# monopoly.net
KiCad netlist of a schematic drawn in EAGLE
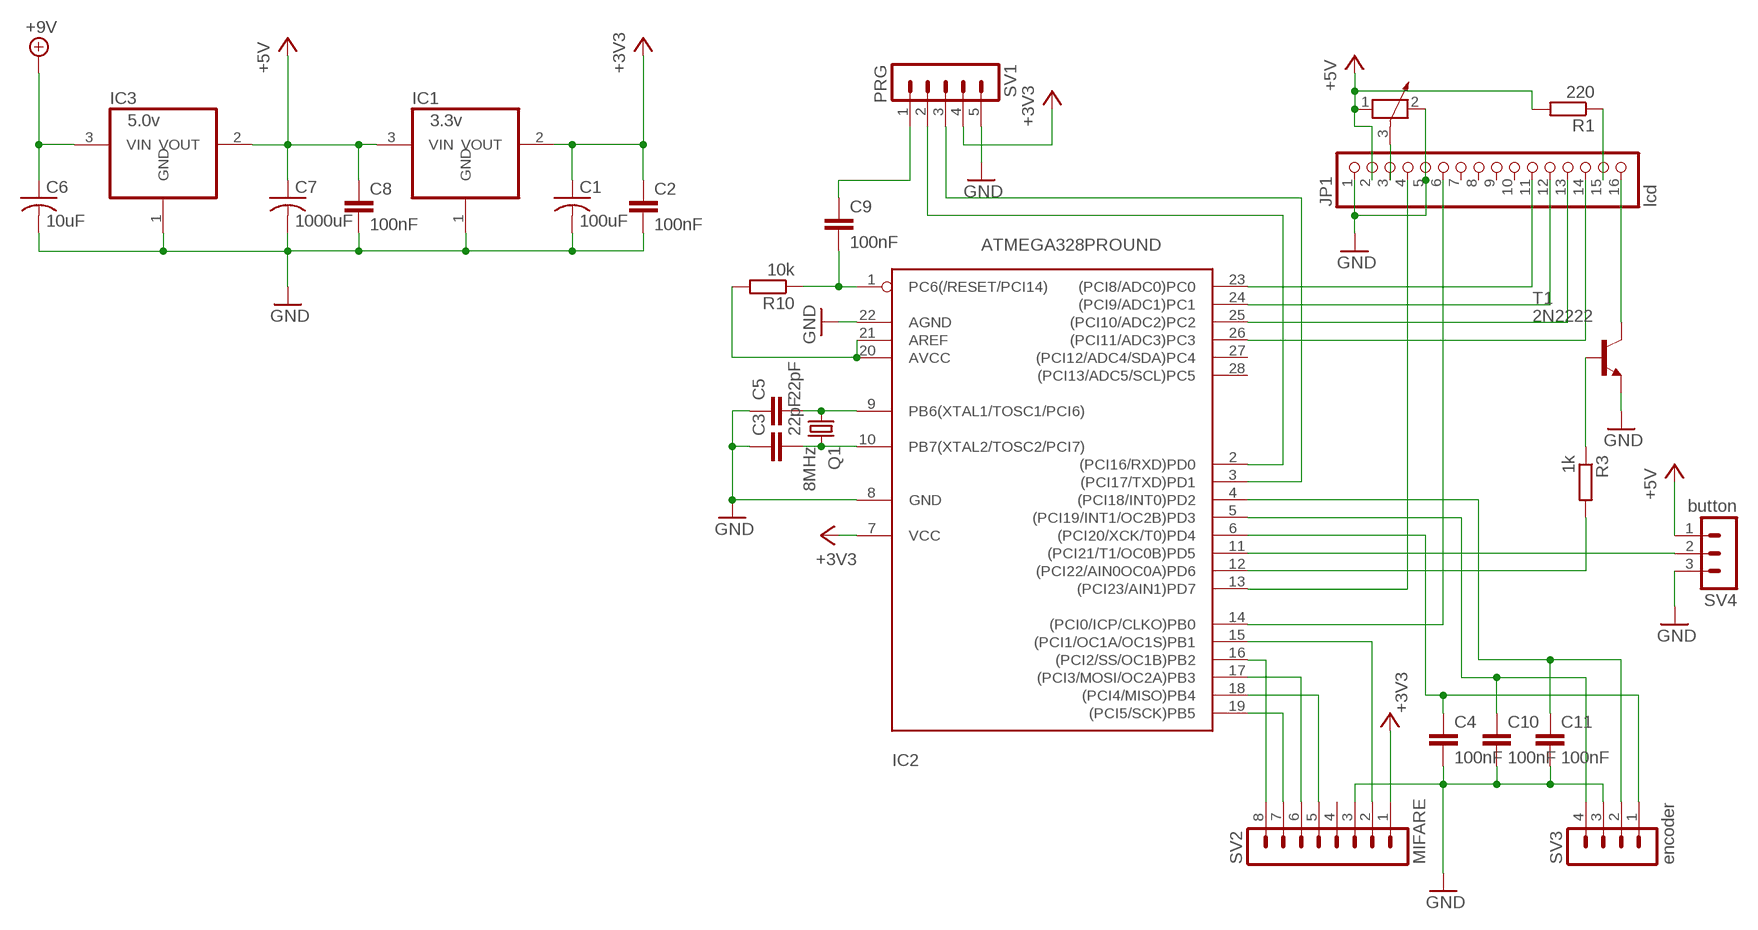
[diagram p0: schematic, sheet 1]

(export (version "E")
  (design (tool "Eeschema 10.0.6"))
  (components
    (comp (ref "C1")
      (value "100uF")
      (footprint "eagle-import:C025-024X044")
      (libsource (lib "eagle-import") (part "C-US025-024X044"))
    )
    (comp (ref "C2")
      (value "100nF")
      (footprint "eagle-import:C2.5-3")
      (libsource (lib "eagle-import") (part "C2,5-3"))
    )
    (comp (ref "C3")
      (value "22pF")
      (footprint "eagle-import:C2.5-3")
      (libsource (lib "eagle-import") (part "C2,5-3"))
    )
    (comp (ref "C4")
      (value "100nF")
      (footprint "eagle-import:C2.5-3")
      (libsource (lib "eagle-import") (part "C2,5-3"))
    )
    (comp (ref "C5")
      (value "22pF")
      (footprint "eagle-import:C2.5-3")
      (libsource (lib "eagle-import") (part "C2,5-3"))
    )
    (comp (ref "C6")
      (value "10uF")
      (footprint "eagle-import:C025-024X044")
      (libsource (lib "eagle-import") (part "C-US025-024X044"))
    )
    (comp (ref "C7")
      (value "1000uF")
      (footprint "eagle-import:C025-024X044")
      (libsource (lib "eagle-import") (part "C-US025-024X044"))
    )
    (comp (ref "C8")
      (value "100nF")
      (footprint "eagle-import:C2.5-3")
      (libsource (lib "eagle-import") (part "C2,5-3"))
    )
    (comp (ref "C9")
      (value "100nF")
      (footprint "eagle-import:C2.5-3")
      (libsource (lib "eagle-import") (part "C2,5-3"))
    )
    (comp (ref "C10")
      (value "100nF")
      (footprint "eagle-import:C2.5-3")
      (libsource (lib "eagle-import") (part "C2,5-3"))
    )
    (comp (ref "C11")
      (value "100nF")
      (footprint "eagle-import:C2.5-3")
      (libsource (lib "eagle-import") (part "C2,5-3"))
    )
    (comp (ref "IC1")
      (value "3.3v")
      (footprint "eagle-import:SOT223")
      (fields (field (name "MPN") "REG1117"))
      (libsource (lib "eagle-import") (part "REG1117"))
    )
    (comp (ref "IC2")
      (value "ATMEGA328PROUND")
      (footprint "eagle-import:DIL28-3-ROUND")
      (libsource (lib "eagle-import") (part "ATMEGA328PROUND"))
    )
    (comp (ref "IC3")
      (value "5.0v")
      (footprint "eagle-import:SOT223")
      (fields (field (name "MPN") "REG1117"))
      (libsource (lib "eagle-import") (part "REG1117"))
    )
    (comp (ref "JP1")
      (value "lcd")
      (footprint "eagle-import:1X16")
      (libsource (lib "eagle-import") (part "PINHD-1X16"))
    )
    (comp (ref "Q1")
      (value "8MHz")
      (footprint "eagle-import:HC18U-V")
      (libsource (lib "eagle-import") (part "CRYSTALHC18U-V"))
    )
    (comp (ref "R1")
      (value "220")
      (footprint "eagle-import:0204_7")
      (libsource (lib "eagle-import") (part "R0204/7"))
    )
    (comp (ref "R2")
      (value "POTENTIOMETER_PT_SPIN")
      (footprint "eagle-import:PT-SPIN")
      (libsource (lib "eagle-import") (part "POTENTIOMETER_PT_SPIN"))
    )
    (comp (ref "R3")
      (value "1k")
      (footprint "eagle-import:0204_7")
      (libsource (lib "eagle-import") (part "R0204/7"))
    )
    (comp (ref "R10")
      (value "10k")
      (footprint "eagle-import:0204_7")
      (libsource (lib "eagle-import") (part "R0204/7"))
    )
    (comp (ref "SV1")
      (value "PRG")
      (footprint "eagle-import:MA05-1")
      (libsource (lib "eagle-import") (part "MA05-1"))
    )
    (comp (ref "SV2")
      (value "MIFARE")
      (footprint "eagle-import:MA08-1W")
      (libsource (lib "eagle-import") (part "MA08-1W"))
    )
    (comp (ref "SV3")
      (value "encoder")
      (footprint "eagle-import:MA04-1")
      (libsource (lib "eagle-import") (part "MA04-1"))
    )
    (comp (ref "SV4")
      (value "button")
      (footprint "eagle-import:MA03-1")
      (libsource (lib "eagle-import") (part "MA03-1"))
    )
    (comp (ref "T1")
      (value "2N2222")
      (footprint "eagle-import:TO18")
      (libsource (lib "eagle-import") (part "2N2222"))
    )
  )
  (nets
    (net (code "1") (name "+3V3") (class "Default")
      (node (ref "C1") (pin "1") (pinfunction "1_1") (pintype "passive"))
      (node (ref "C2") (pin "1") (pinfunction "1_1") (pintype "passive"))
      (node (ref "IC1") (pin "2") (pinfunction "VOUT_2") (pintype "output"))
      (node (ref "IC2") (pin "7") (pinfunction "VCC_7") (pintype "bidirectional"))
      (node (ref "SV1") (pin "4") (pinfunction "4_4") (pintype "passive"))
      (node (ref "SV2") (pin "1") (pinfunction "1_1") (pintype "passive"))
    )
    (net (code "2") (name "+5V") (class "Default")
      (node (ref "C7") (pin "1") (pinfunction "1_1") (pintype "passive"))
      (node (ref "C8") (pin "1") (pinfunction "1_1") (pintype "passive"))
      (node (ref "IC1") (pin "3") (pinfunction "VIN_3") (pintype "input"))
      (node (ref "IC3") (pin "2") (pinfunction "VOUT_2") (pintype "output"))
      (node (ref "JP1") (pin "2") (pinfunction "2_2") (pintype "passive"))
      (node (ref "R1") (pin "2") (pinfunction "2_2") (pintype "passive"))
      (node (ref "R2") (pin "1") (pinfunction "1_1") (pintype "passive"))
      (node (ref "SV4") (pin "1") (pinfunction "1_1") (pintype "passive"))
    )
    (net (code "3") (name "+9V") (class "Default")
      (node (ref "C6") (pin "1") (pinfunction "1_1") (pintype "passive"))
      (node (ref "IC3") (pin "3") (pinfunction "VIN_3") (pintype "input"))
    )
    (net (code "4") (name "GND") (class "Default")
      (node (ref "C1") (pin "2") (pinfunction "2_2") (pintype "passive"))
      (node (ref "C10") (pin "2") (pinfunction "2_2") (pintype "passive"))
      (node (ref "C11") (pin "2") (pinfunction "2_2") (pintype "passive"))
      (node (ref "C2") (pin "2") (pinfunction "2_2") (pintype "passive"))
      (node (ref "C3") (pin "1") (pinfunction "1_1") (pintype "passive"))
      (node (ref "C4") (pin "2") (pinfunction "2_2") (pintype "passive"))
      (node (ref "C5") (pin "1") (pinfunction "1_1") (pintype "passive"))
      (node (ref "C6") (pin "2") (pinfunction "2_2") (pintype "passive"))
      (node (ref "C7") (pin "2") (pinfunction "2_2") (pintype "passive"))
      (node (ref "C8") (pin "2") (pinfunction "2_2") (pintype "passive"))
      (node (ref "IC1") (pin "1") (pinfunction "GND_1") (pintype "power_in"))
      (node (ref "IC2") (pin "22") (pinfunction "AGND_22") (pintype "bidirectional"))
      (node (ref "IC2") (pin "8") (pinfunction "GND_8") (pintype "bidirectional"))
      (node (ref "IC3") (pin "1") (pinfunction "GND_1") (pintype "power_in"))
      (node (ref "JP1") (pin "1") (pinfunction "1_1") (pintype "passive"))
      (node (ref "JP1") (pin "5") (pinfunction "5_5") (pintype "passive"))
      (node (ref "R2") (pin "2") (pinfunction "2_2") (pintype "passive"))
      (node (ref "SV1") (pin "5") (pinfunction "5_5") (pintype "passive"))
      (node (ref "SV2") (pin "3") (pinfunction "3_3") (pintype "passive"))
      (node (ref "SV3") (pin "3") (pinfunction "3_3") (pintype "passive"))
      (node (ref "SV4") (pin "3") (pinfunction "3_3") (pintype "passive"))
      (node (ref "T1") (pin "1") (pinfunction "E_1") (pintype "passive"))
    )
    (net (code "5") (name "Net-(C9-Pad1)") (class "Default")
      (node (ref "C9") (pin "1") (pinfunction "1_1") (pintype "passive"))
      (node (ref "SV1") (pin "1") (pinfunction "1_1") (pintype "passive"))
    )
    (net (code "6") (name "Net-(IC2-(PCI0{slash}ICP{slash}CLKO)PB0)") (class "Default")
      (node (ref "IC2") (pin "14") (pinfunction "(PCI0/ICP/CLKO)PB0_14") (pintype "bidirectional"))
      (node (ref "JP1") (pin "6") (pinfunction "6_6") (pintype "passive"))
    )
    (net (code "7") (name "Net-(IC2-(PCI1{slash}OC1A{slash}OC1S)PB1)") (class "Default")
      (node (ref "IC2") (pin "15") (pinfunction "(PCI1/OC1A/OC1S)PB1_15") (pintype "bidirectional"))
      (node (ref "SV2") (pin "2") (pinfunction "2_2") (pintype "passive"))
    )
    (net (code "8") (name "Net-(IC2-(PCI2{slash}SS{slash}OC1B)PB2)") (class "Default")
      (node (ref "IC2") (pin "16") (pinfunction "(PCI2/SS/OC1B)PB2_16") (pintype "bidirectional"))
      (node (ref "SV2") (pin "8") (pinfunction "8_8") (pintype "passive"))
    )
    (net (code "9") (name "Net-(IC2-(PCI3{slash}MOSI{slash}OC2A)PB3)") (class "Default")
      (node (ref "IC2") (pin "17") (pinfunction "(PCI3/MOSI/OC2A)PB3_17") (pintype "bidirectional"))
      (node (ref "SV2") (pin "6") (pinfunction "6_6") (pintype "passive"))
    )
    (net (code "10") (name "Net-(IC2-(PCI4{slash}MISO)PB4)") (class "Default")
      (node (ref "IC2") (pin "18") (pinfunction "(PCI4/MISO)PB4_18") (pintype "bidirectional"))
      (node (ref "SV2") (pin "5") (pinfunction "5_5") (pintype "passive"))
    )
    (net (code "11") (name "Net-(IC2-(PCI5{slash}SCK)PB5)") (class "Default")
      (node (ref "IC2") (pin "19") (pinfunction "(PCI5/SCK)PB5_19") (pintype "bidirectional"))
      (node (ref "SV2") (pin "7") (pinfunction "7_7") (pintype "passive"))
    )
    (net (code "12") (name "Net-(IC2-(PCI8{slash}ADC0)PC0)") (class "Default")
      (node (ref "IC2") (pin "23") (pinfunction "(PCI8/ADC0)PC0_23") (pintype "bidirectional"))
      (node (ref "JP1") (pin "11") (pinfunction "11_11") (pintype "passive"))
    )
    (net (code "13") (name "Net-(IC2-(PCI9{slash}ADC1)PC1)") (class "Default")
      (node (ref "IC2") (pin "24") (pinfunction "(PCI9/ADC1)PC1_24") (pintype "bidirectional"))
      (node (ref "JP1") (pin "12") (pinfunction "12_12") (pintype "passive"))
    )
    (net (code "14") (name "Net-(IC2-(PCI10{slash}ADC2)PC2)") (class "Default")
      (node (ref "IC2") (pin "25") (pinfunction "(PCI10/ADC2)PC2_25") (pintype "bidirectional"))
      (node (ref "JP1") (pin "13") (pinfunction "13_13") (pintype "passive"))
    )
    (net (code "15") (name "Net-(IC2-(PCI11{slash}ADC3)PC3)") (class "Default")
      (node (ref "IC2") (pin "26") (pinfunction "(PCI11/ADC3)PC3_26") (pintype "bidirectional"))
      (node (ref "JP1") (pin "14") (pinfunction "14_14") (pintype "passive"))
    )
    (net (code "16") (name "Net-(IC2-(PCI16{slash}RXD)PD0)") (class "Default")
      (node (ref "IC2") (pin "2") (pinfunction "(PCI16/RXD)PD0_2") (pintype "bidirectional"))
      (node (ref "SV1") (pin "2") (pinfunction "2_2") (pintype "passive"))
    )
    (net (code "17") (name "Net-(IC2-(PCI17{slash}TXD)PD1)") (class "Default")
      (node (ref "IC2") (pin "3") (pinfunction "(PCI17/TXD)PD1_3") (pintype "bidirectional"))
      (node (ref "SV1") (pin "3") (pinfunction "3_3") (pintype "passive"))
    )
    (net (code "18") (name "Net-(IC2-(PCI18{slash}INT0)PD2)") (class "Default")
      (node (ref "C11") (pin "1") (pinfunction "1_1") (pintype "passive"))
      (node (ref "IC2") (pin "4") (pinfunction "(PCI18/INT0)PD2_4") (pintype "bidirectional"))
      (node (ref "SV3") (pin "2") (pinfunction "2_2") (pintype "passive"))
    )
    (net (code "19") (name "Net-(IC2-(PCI19{slash}INT1{slash}OC2B)PD3)") (class "Default")
      (node (ref "C10") (pin "1") (pinfunction "1_1") (pintype "passive"))
      (node (ref "IC2") (pin "5") (pinfunction "(PCI19/INT1/OC2B)PD3_5") (pintype "bidirectional"))
      (node (ref "SV3") (pin "4") (pinfunction "4_4") (pintype "passive"))
    )
    (net (code "20") (name "Net-(IC2-(PCI20{slash}XCK{slash}T0)PD4)") (class "Default")
      (node (ref "C4") (pin "1") (pinfunction "1_1") (pintype "passive"))
      (node (ref "IC2") (pin "6") (pinfunction "(PCI20/XCK/T0)PD4_6") (pintype "bidirectional"))
      (node (ref "SV3") (pin "1") (pinfunction "1_1") (pintype "passive"))
    )
    (net (code "21") (name "Net-(IC2-(PCI21{slash}T1{slash}OC0B)PD5)") (class "Default")
      (node (ref "IC2") (pin "11") (pinfunction "(PCI21/T1/OC0B)PD5_11") (pintype "bidirectional"))
      (node (ref "SV4") (pin "2") (pinfunction "2_2") (pintype "passive"))
    )
    (net (code "22") (name "Net-(IC2-(PCI22{slash}AIN0OC0A)PD6)") (class "Default")
      (node (ref "IC2") (pin "12") (pinfunction "(PCI22/AIN0OC0A)PD6_12") (pintype "bidirectional"))
      (node (ref "R3") (pin "2") (pinfunction "2_2") (pintype "passive"))
    )
    (net (code "23") (name "Net-(IC2-(PCI23{slash}AIN1)PD7)") (class "Default")
      (node (ref "IC2") (pin "13") (pinfunction "(PCI23/AIN1)PD7_13") (pintype "bidirectional"))
      (node (ref "JP1") (pin "4") (pinfunction "4_4") (pintype "passive"))
    )
    (net (code "24") (name "Net-(IC2-AREF)") (class "Default")
      (node (ref "IC2") (pin "20") (pinfunction "AVCC_20") (pintype "bidirectional"))
      (node (ref "IC2") (pin "21") (pinfunction "AREF_21") (pintype "bidirectional"))
      (node (ref "R10") (pin "2") (pinfunction "2_2") (pintype "passive"))
    )
    (net (code "25") (name "Net-(IC2-PB6(XTAL1{slash}TOSC1{slash}PCI6))") (class "Default")
      (node (ref "C5") (pin "2") (pinfunction "2_2") (pintype "passive"))
      (node (ref "IC2") (pin "9") (pinfunction "PB6(XTAL1/TOSC1/PCI6)_9") (pintype "bidirectional"))
      (node (ref "Q1") (pin "1") (pinfunction "1_1") (pintype "passive"))
    )
    (net (code "26") (name "Net-(IC2-PB7(XTAL2{slash}TOSC2{slash}PCI7))") (class "Default")
      (node (ref "C3") (pin "2") (pinfunction "2_2") (pintype "passive"))
      (node (ref "IC2") (pin "10") (pinfunction "PB7(XTAL2/TOSC2/PCI7)_10") (pintype "bidirectional"))
      (node (ref "Q1") (pin "2") (pinfunction "2_2") (pintype "passive"))
    )
    (net (code "27") (name "Net-(IC2-PC6({slash}RESET{slash}PCI14))") (class "Default")
      (node (ref "C9") (pin "2") (pinfunction "2_2") (pintype "passive"))
      (node (ref "IC2") (pin "1") (pinfunction "PC6(/RESET/PCI14)_1") (pintype "bidirectional"))
      (node (ref "R10") (pin "1") (pinfunction "1_1") (pintype "passive"))
    )
    (net (code "28") (name "Net-(JP1-Pad3)") (class "Default")
      (node (ref "JP1") (pin "3") (pinfunction "3_3") (pintype "passive"))
      (node (ref "R2") (pin "3") (pinfunction "3_3") (pintype "passive"))
    )
    (net (code "29") (name "Net-(JP1-Pad15)") (class "Default")
      (node (ref "JP1") (pin "15") (pinfunction "15_15") (pintype "passive"))
      (node (ref "R1") (pin "1") (pinfunction "1_1") (pintype "passive"))
    )
    (net (code "30") (name "Net-(T1-B)") (class "Default")
      (node (ref "R3") (pin "1") (pinfunction "1_1") (pintype "passive"))
      (node (ref "T1") (pin "2") (pinfunction "B_2") (pintype "passive"))
    )
    (net (code "31") (name "Net-(T1-C)") (class "Default")
      (node (ref "JP1") (pin "16") (pinfunction "16_16") (pintype "passive"))
      (node (ref "T1") (pin "3") (pinfunction "C_3") (pintype "passive"))
    )
    (net (code "32") (name "unconnected-(IC2-(PCI12{slash}ADC4{slash}SDA)PC4-Pad27)") (class "Default")
      (node (ref "IC2") (pin "27") (pinfunction "(PCI12/ADC4/SDA)PC4_27") (pintype "bidirectional"))
    )
    (net (code "33") (name "unconnected-(IC2-(PCI13{slash}ADC5{slash}SCL)PC5-Pad28)") (class "Default")
      (node (ref "IC2") (pin "28") (pinfunction "(PCI13/ADC5/SCL)PC5_28") (pintype "bidirectional"))
    )
    (net (code "34") (name "unconnected-(JP1-Pad7)") (class "Default")
      (node (ref "JP1") (pin "7") (pinfunction "7_7") (pintype "passive"))
    )
    (net (code "35") (name "unconnected-(JP1-Pad8)") (class "Default")
      (node (ref "JP1") (pin "8") (pinfunction "8_8") (pintype "passive"))
    )
    (net (code "36") (name "unconnected-(JP1-Pad9)") (class "Default")
      (node (ref "JP1") (pin "9") (pinfunction "9_9") (pintype "passive"))
    )
    (net (code "37") (name "unconnected-(JP1-Pad10)") (class "Default")
      (node (ref "JP1") (pin "10") (pinfunction "10_10") (pintype "passive"))
    )
    (net (code "38") (name "unconnected-(SV2-Pad4)") (class "Default")
      (node (ref "SV2") (pin "4") (pinfunction "4_4") (pintype "passive"))
    )
  )
)
